# Application.net
KiCad netlist of a schematic drawn in EAGLE
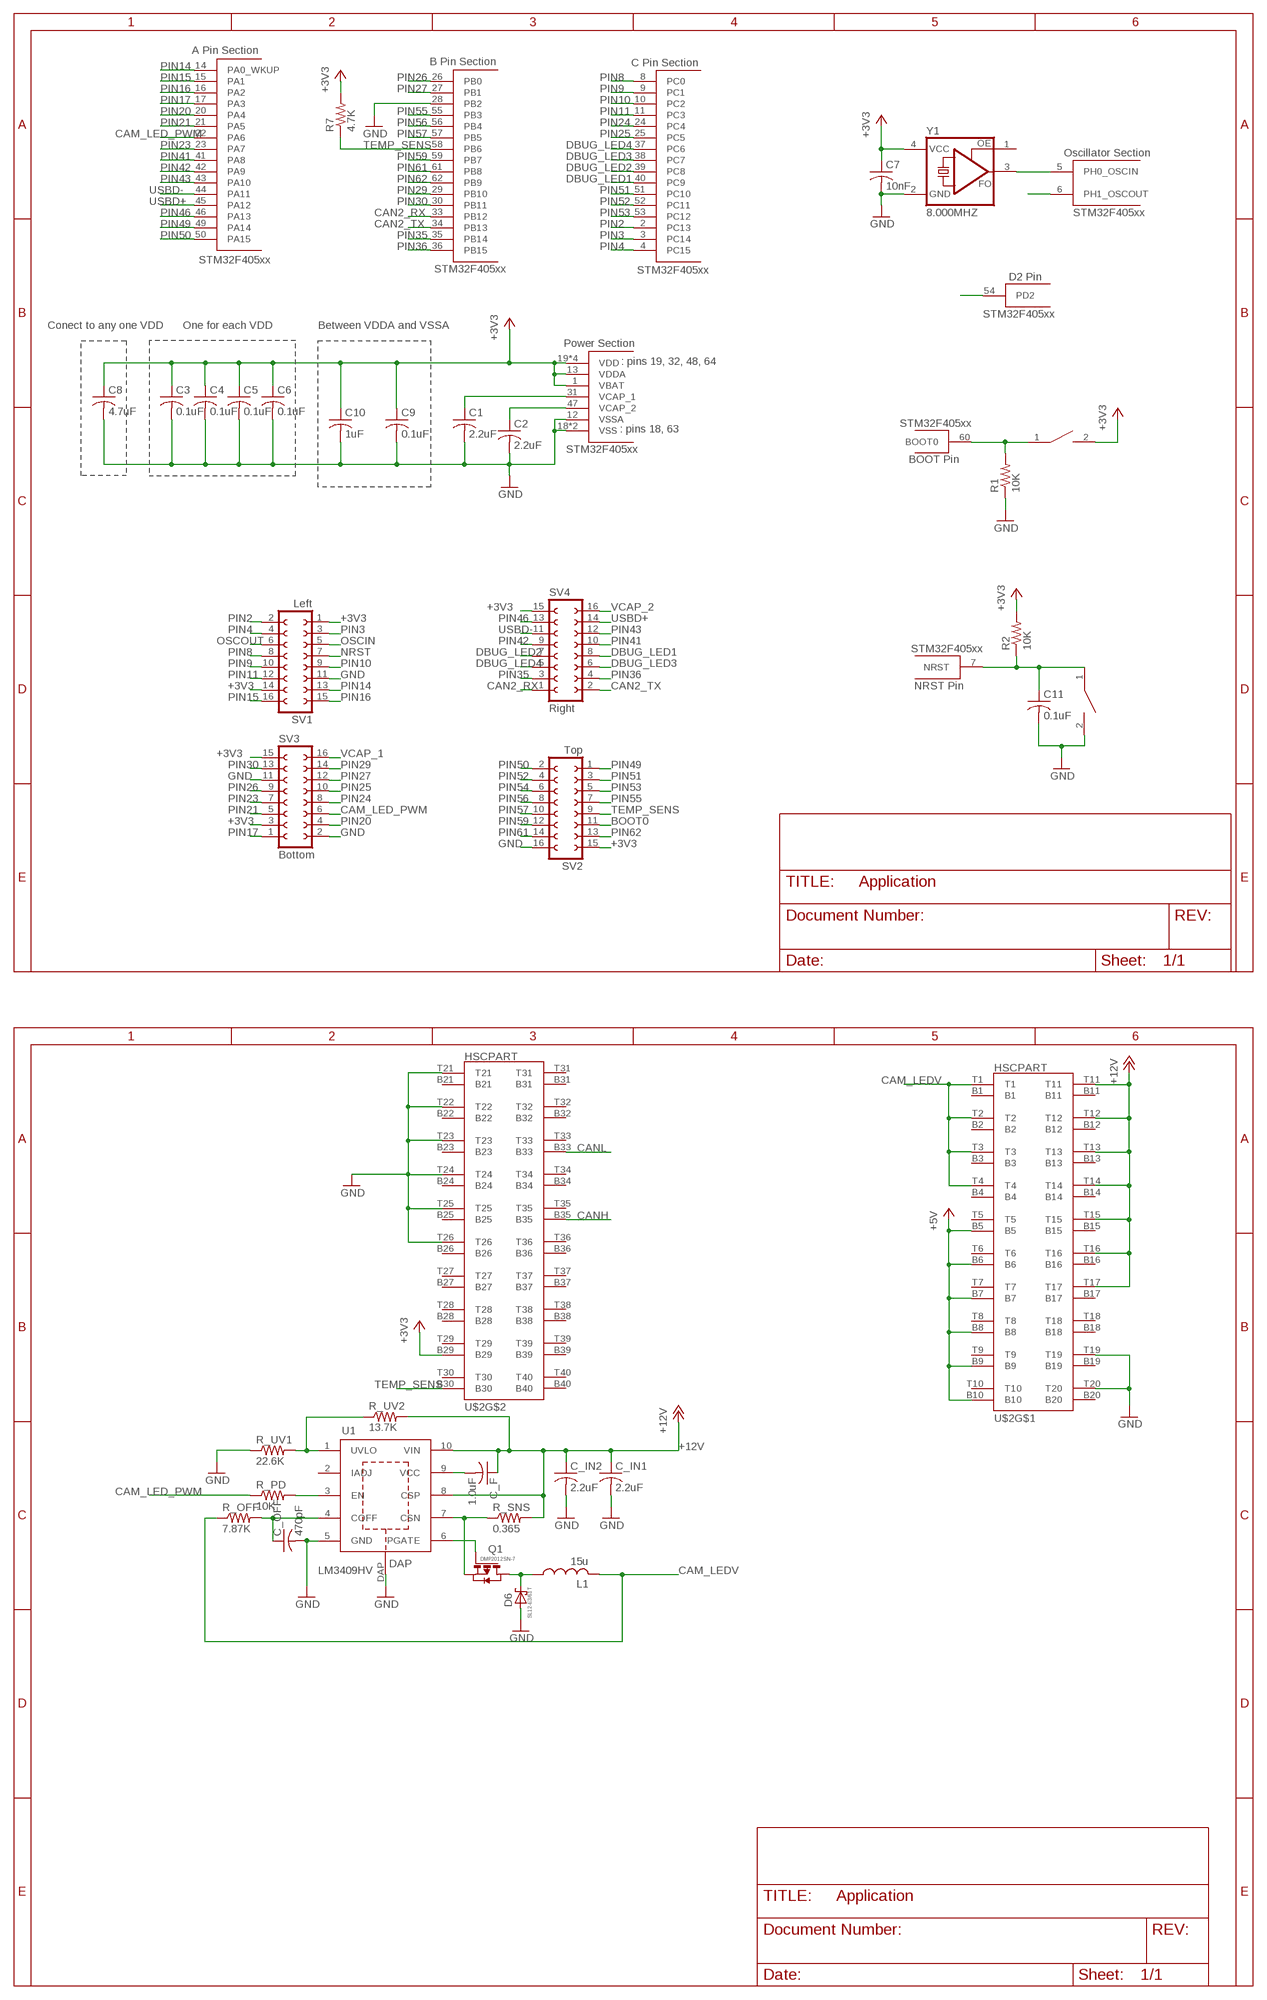
[diagram p0: schematic, sheet 1, part 1 of 2]
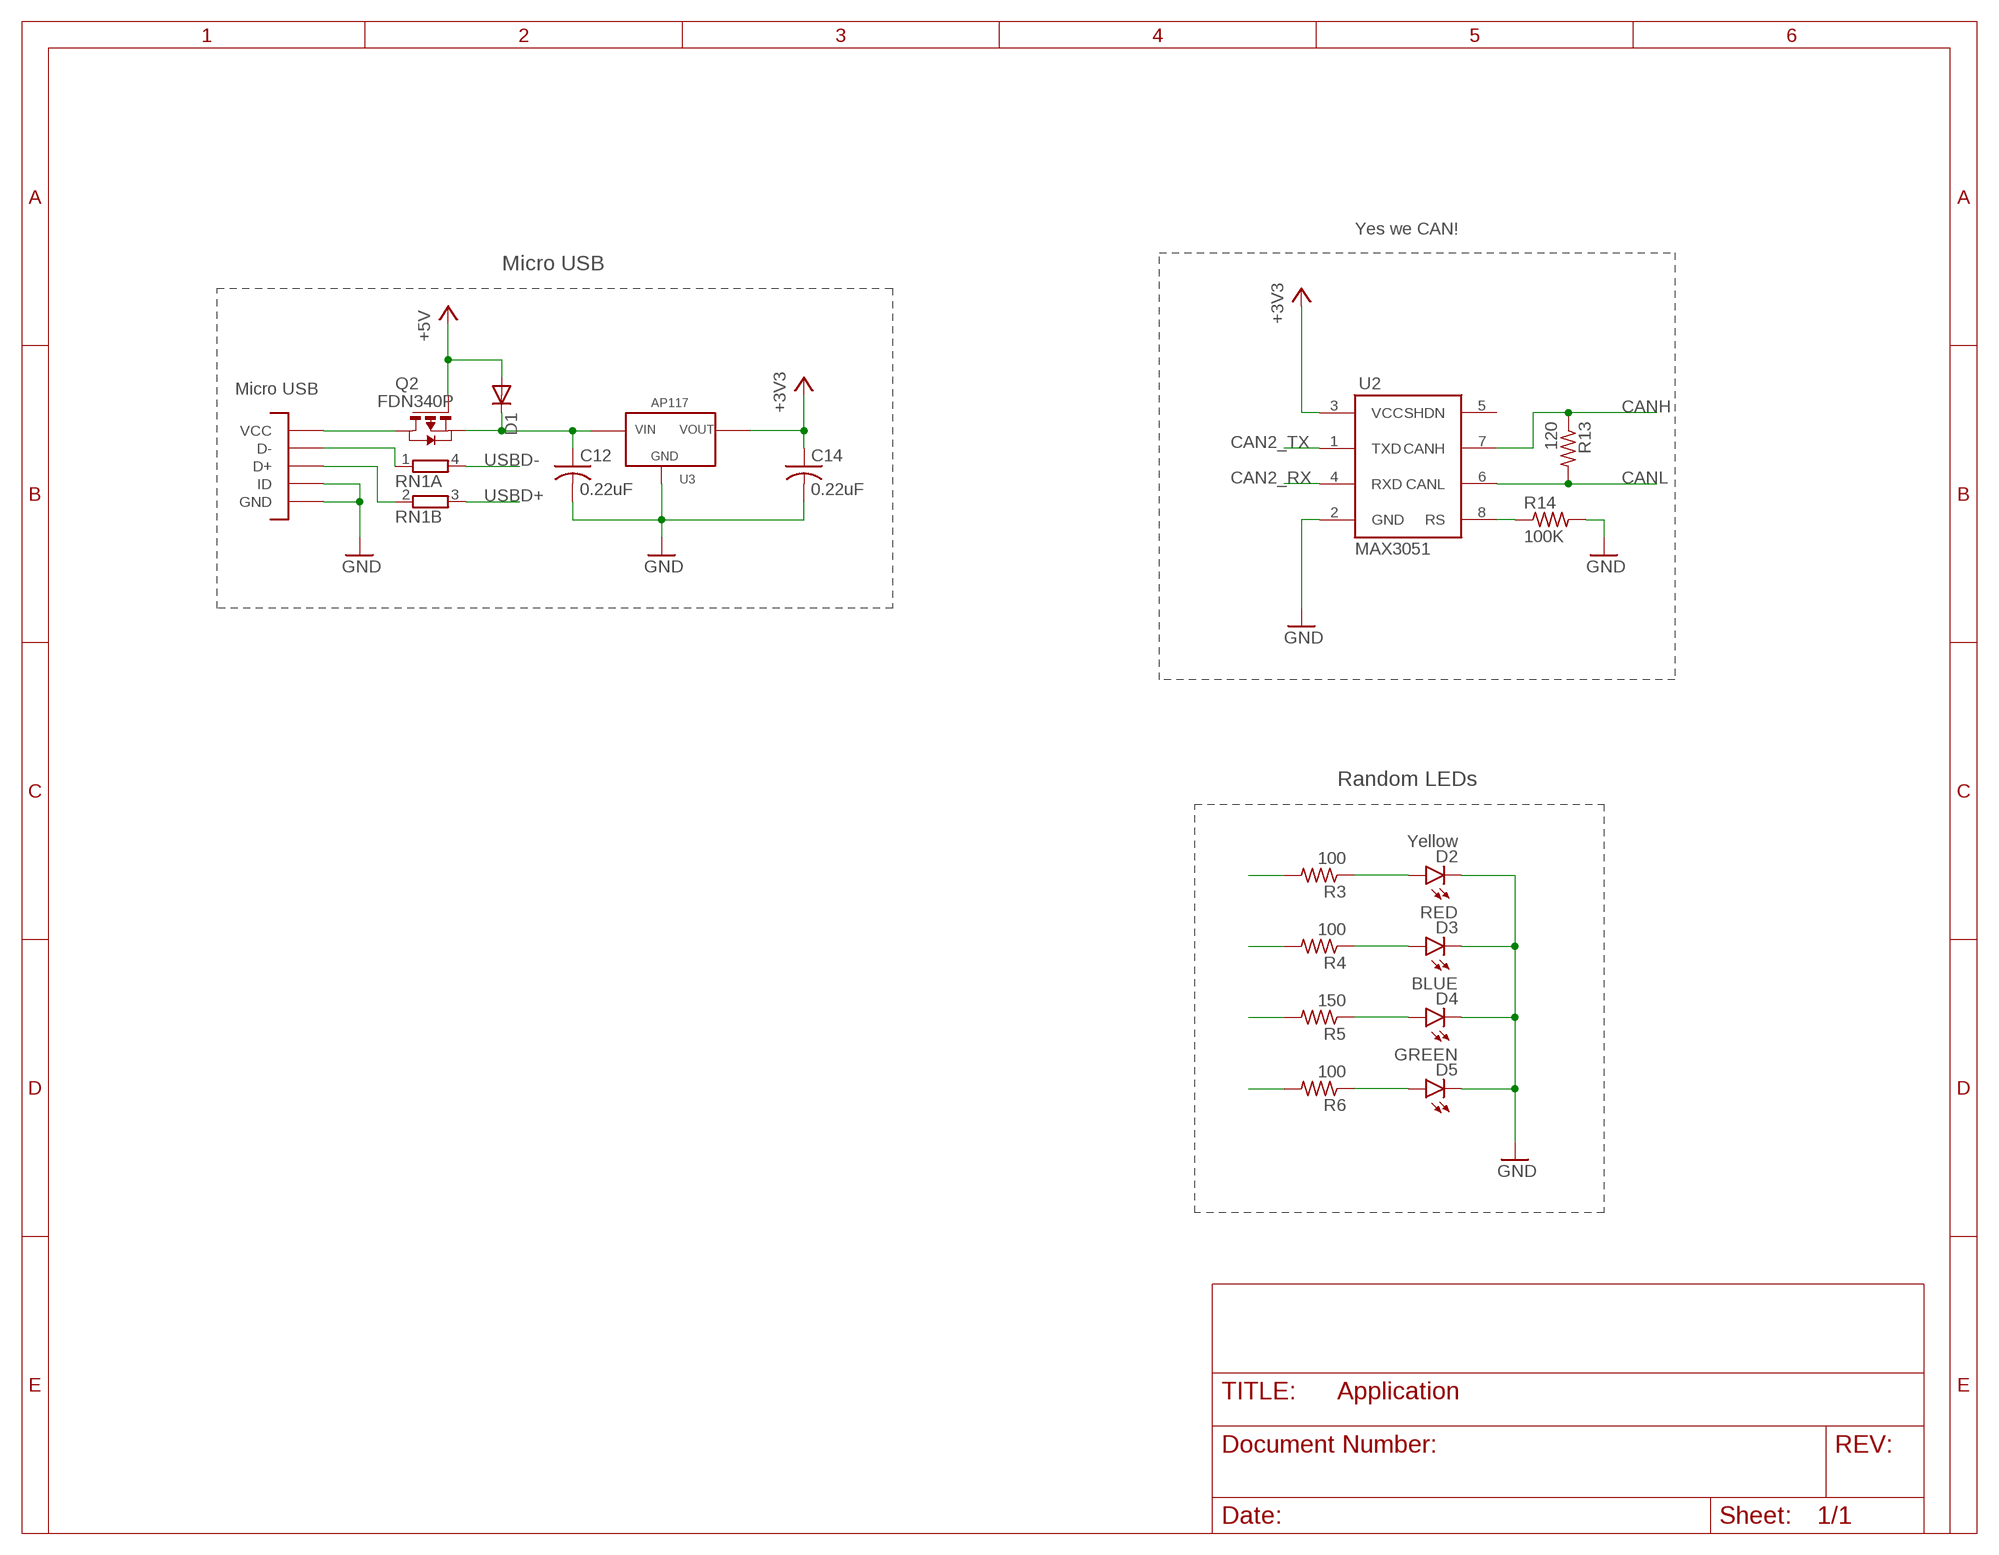
[diagram p1: schematic, sheet 1, part 2 of 2]

(export (version "E")
  (design (tool "Eeschema 10.0.6"))
  (components
    (comp (ref "C1")
      (value "2.2uF")
      (footprint "eagle-import:C0603")
      (libsource (lib "eagle-import") (part "C-USC0603"))
    )
    (comp (ref "C2")
      (value "2.2uF")
      (footprint "eagle-import:C0603")
      (libsource (lib "eagle-import") (part "C-USC0603"))
    )
    (comp (ref "C3")
      (value "0.1uF")
      (footprint "eagle-import:C0603")
      (libsource (lib "eagle-import") (part "C-USC0603"))
    )
    (comp (ref "C4")
      (value "0.1uF")
      (footprint "eagle-import:C0603")
      (libsource (lib "eagle-import") (part "C-USC0603"))
    )
    (comp (ref "C5")
      (value "0.1uF")
      (footprint "eagle-import:C0603")
      (libsource (lib "eagle-import") (part "C-USC0603"))
    )
    (comp (ref "C6")
      (value "0.1uF")
      (footprint "eagle-import:C0603")
      (libsource (lib "eagle-import") (part "C-USC0603"))
    )
    (comp (ref "C7")
      (value "10nF")
      (footprint "eagle-import:C0603")
      (libsource (lib "eagle-import") (part "C-USC0603"))
    )
    (comp (ref "C8")
      (value "4.7uF")
      (footprint "eagle-import:C0603")
      (libsource (lib "eagle-import") (part "C-USC0603"))
    )
    (comp (ref "C9")
      (value "0.1uF")
      (footprint "eagle-import:C0603")
      (libsource (lib "eagle-import") (part "C-USC0603"))
    )
    (comp (ref "C10")
      (value "1uF")
      (footprint "eagle-import:C0603")
      (libsource (lib "eagle-import") (part "C-USC0603"))
    )
    (comp (ref "C11")
      (value "0.1uF")
      (footprint "eagle-import:C0603")
      (libsource (lib "eagle-import") (part "C-USC0603"))
    )
    (comp (ref "C12")
      (value "0.22uF")
      (footprint "eagle-import:C0603")
      (libsource (lib "eagle-import") (part "C-USC0603"))
    )
    (comp (ref "C14")
      (value "0.22uF")
      (footprint "eagle-import:C0603")
      (libsource (lib "eagle-import") (part "C-USC0603"))
    )
    (comp (ref "C_F")
      (value "1.0uF")
      (footprint "eagle-import:C0603")
      (libsource (lib "eagle-import") (part "resistor_C-USC0603"))
    )
    (comp (ref "C_IN1")
      (value "2.2uF")
      (footprint "eagle-import:C0603")
      (libsource (lib "eagle-import") (part "resistor_C-USC0603"))
    )
    (comp (ref "C_IN2")
      (value "2.2uF")
      (footprint "eagle-import:C0603")
      (libsource (lib "eagle-import") (part "resistor_C-USC0603"))
    )
    (comp (ref "C_OFF")
      (value "470pF")
      (footprint "eagle-import:C0603")
      (libsource (lib "eagle-import") (part "resistor_C-USC0603"))
    )
    (comp (ref "D1")
      (value "DIODE-DO-214AC")
      (footprint "eagle-import:DO-214AC")
      (libsource (lib "eagle-import") (part "DIODE-DO-214AC"))
    )
    (comp (ref "D2")
      (value "Yellow")
      (footprint "eagle-import:LED-0603")
      (libsource (lib "eagle-import") (part "LED-YELLOW0603"))
    )
    (comp (ref "D3")
      (value "RED")
      (footprint "eagle-import:LED-0603")
      (libsource (lib "eagle-import") (part "LED-RED0603"))
    )
    (comp (ref "D4")
      (value "BLUE")
      (footprint "eagle-import:LED-0603")
      (libsource (lib "eagle-import") (part "LED-BLUE0603"))
    )
    (comp (ref "D5")
      (value "GREEN")
      (footprint "eagle-import:LED-0603")
      (libsource (lib "eagle-import") (part "LED-GREEN0603"))
    )
    (comp (ref "D6")
      (value "SL12-E3/61T")
      (footprint "eagle-import:SL12-E3_61T")
      (libsource (lib "eagle-import") (part "SL12-E3/61T"))
    )
    (comp (ref "L1")
      (value "15u")
      (footprint "eagle-import:SRN8040")
      (libsource (lib "eagle-import") (part "SRN8040"))
    )
    (comp (ref "Q1")
      (value "DMP2012SN-7")
      (footprint "eagle-import:DMP2012SN-7")
      (libsource (lib "eagle-import") (part "DMP2012SN-7"))
    )
    (comp (ref "Q2")
      (value "FDN340P")
      (footprint "eagle-import:SOT-23")
      (libsource (lib "eagle-import") (part "FDN340P"))
    )
    (comp (ref "R1")
      (value "10K")
      (footprint "eagle-import:R0603")
      (libsource (lib "eagle-import") (part "rcl_R-US_R0603"))
    )
    (comp (ref "R2")
      (value "10K")
      (footprint "eagle-import:R0603")
      (libsource (lib "eagle-import") (part "rcl_R-US_R0603"))
    )
    (comp (ref "R3")
      (value "100")
      (footprint "eagle-import:R0603")
      (libsource (lib "eagle-import") (part "rcl_R-US_R0603"))
    )
    (comp (ref "R4")
      (value "100")
      (footprint "eagle-import:R0603")
      (libsource (lib "eagle-import") (part "rcl_R-US_R0603"))
    )
    (comp (ref "R5")
      (value "150")
      (footprint "eagle-import:R0603")
      (libsource (lib "eagle-import") (part "rcl_R-US_R0603"))
    )
    (comp (ref "R6")
      (value "100")
      (footprint "eagle-import:R0603")
      (libsource (lib "eagle-import") (part "rcl_R-US_R0603"))
    )
    (comp (ref "R7")
      (value "4.7K")
      (footprint "eagle-import:R0603")
      (libsource (lib "eagle-import") (part "rcl_R-US_R0603"))
    )
    (comp (ref "R13")
      (value "120")
      (footprint "eagle-import:R0603")
      (libsource (lib "eagle-import") (part "rcl_R-US_R0603"))
    )
    (comp (ref "R14")
      (value "100K")
      (footprint "eagle-import:R0603")
      (libsource (lib "eagle-import") (part "rcl_R-US_R0603"))
    )
    (comp (ref "RN1")
      (value "2R-NEXBV4V")
      (footprint "eagle-import:EXBV4V")
      (fields (field (name "MF") "Rohm Semiconductor") (field (name "MPN") "MNR12ERAPJ220"))
      (libsource (lib "eagle-import") (part "2R-NEXBV4V"))
    )
    (comp (ref "R_OFF")
      (value "7.87K")
      (footprint "eagle-import:R0603")
      (libsource (lib "eagle-import") (part "R-US_R0603"))
    )
    (comp (ref "R_PD")
      (value "10K")
      (footprint "eagle-import:R0603")
      (libsource (lib "eagle-import") (part "R-US_R0603"))
    )
    (comp (ref "R_SNS")
      (value "0.365")
      (footprint "eagle-import:R2512")
      (libsource (lib "eagle-import") (part "R-US_R2512"))
    )
    (comp (ref "R_UV1")
      (value "22.6K")
      (footprint "eagle-import:R0603")
      (libsource (lib "eagle-import") (part "R-US_R0603"))
    )
    (comp (ref "R_UV2")
      (value "13.7K")
      (footprint "eagle-import:R0603")
      (libsource (lib "eagle-import") (part "R-US_R0603"))
    )
    (comp (ref "S1")
      (value "BOOT")
      (footprint "eagle-import:SW_2512")
      (libsource (lib "eagle-import") (part "SWITCH"))
    )
    (comp (ref "S2")
      (value "RESET")
      (footprint "eagle-import:SW_2512")
      (libsource (lib "eagle-import") (part "SWITCH"))
    )
    (comp (ref "SV1")
      (value "Left")
      (footprint "eagle-import:FE08-2")
      (libsource (lib "eagle-import") (part "FE08-2"))
    )
    (comp (ref "SV2")
      (value "Top")
      (footprint "eagle-import:FE08-2")
      (libsource (lib "eagle-import") (part "FE08-2"))
    )
    (comp (ref "SV3")
      (value "Bottom")
      (footprint "eagle-import:FE08-2")
      (libsource (lib "eagle-import") (part "FE08-2"))
    )
    (comp (ref "SV4")
      (value "Right")
      (footprint "eagle-import:FE08-2")
      (libsource (lib "eagle-import") (part "FE08-2"))
    )
    (comp (ref "U$2")
      (value "HSCPART")
      (footprint "eagle-import:HSC8-40PINOUUT")
      (libsource (lib "eagle-import") (part "HSCPART"))
    )
    (comp (ref "U1")
      (value "LM3409HV")
      (footprint "eagle-import:VSSOP-10")
      (libsource (lib "eagle-import") (part "LM3409HV'LM3409HV'"))
    )
    (comp (ref "U2")
      (value "MAX3051")
      (footprint "eagle-import:SOT23-8L")
      (libsource (lib "eagle-import") (part "MAX3051MAX3051"))
    )
    (comp (ref "U3")
      (value "U3")
      (footprint "eagle-import:SOT223")
      (libsource (lib "eagle-import") (part "AP1117_LIN_REG"))
    )
    (comp (ref "U4")
      (value "STM32F405")
      (footprint "eagle-import:LQFP64")
      (libsource (lib "eagle-import") (part "STM32F405"))
    )
    (comp (ref "U5")
      (value "MICROUSB")
      (footprint "eagle-import:MICRO_B")
      (libsource (lib "eagle-import") (part "MICROUSB"))
    )
    (comp (ref "Y1")
      (value "8.000MHZ")
      (footprint "eagle-import:ASF")
      (libsource (lib "eagle-import") (part "ASF"))
    )
  )
  (nets
    (net (code "1") (name "+3V3") (class "Default")
      (node (ref "C10") (pin "1") (pinfunction "1_1") (pintype "passive"))
      (node (ref "C14") (pin "1") (pinfunction "1_1") (pintype "passive"))
      (node (ref "C3") (pin "1") (pinfunction "1_1") (pintype "passive"))
      (node (ref "C4") (pin "1") (pinfunction "1_1") (pintype "passive"))
      (node (ref "C5") (pin "1") (pinfunction "1_1") (pintype "passive"))
      (node (ref "C6") (pin "1") (pinfunction "1_1") (pintype "passive"))
      (node (ref "C7") (pin "1") (pinfunction "1_1") (pintype "passive"))
      (node (ref "C8") (pin "1") (pinfunction "1_1") (pintype "passive"))
      (node (ref "C9") (pin "1") (pinfunction "1_1") (pintype "passive"))
      (node (ref "R2") (pin "2") (pinfunction "2_2") (pintype "passive"))
      (node (ref "R7") (pin "2") (pinfunction "2_2") (pintype "passive"))
      (node (ref "S1") (pin "2") (pinfunction "P$2_2") (pintype "bidirectional"))
      (node (ref "SV1") (pin "1") (pinfunction "1_1") (pintype "passive"))
      (node (ref "SV1") (pin "14") (pinfunction "14_14") (pintype "passive"))
      (node (ref "SV2") (pin "15") (pinfunction "15_15") (pintype "passive"))
      (node (ref "SV3") (pin "15") (pinfunction "15_15") (pintype "passive"))
      (node (ref "SV3") (pin "3") (pinfunction "3_3") (pintype "passive"))
      (node (ref "SV4") (pin "15") (pinfunction "15_15") (pintype "passive"))
      (node (ref "U$2") (pin "B29") (pinfunction "B29_B29") (pintype "bidirectional"))
      (node (ref "U2") (pin "3") (pinfunction "VCC_3") (pintype "bidirectional"))
      (node (ref "U3") (pin "TAB") (pinfunction "VOUT_TAB") (pintype "output"))
      (node (ref "U3") (pin "VOUT") (pinfunction "VOUT_VOUT") (pintype "output"))
      (node (ref "U4") (pin "1") (pinfunction "VBAT_1") (pintype "bidirectional"))
      (node (ref "U4") (pin "13") (pinfunction "VDDA_13") (pintype "bidirectional"))
      (node (ref "U4") (pin "19") (pinfunction "VDD_19") (pintype "bidirectional"))
      (node (ref "U4") (pin "32") (pinfunction "VDD_32") (pintype "bidirectional"))
      (node (ref "U4") (pin "48") (pinfunction "VDD_48") (pintype "bidirectional"))
      (node (ref "U4") (pin "64") (pinfunction "VDD_64") (pintype "bidirectional"))
      (node (ref "Y1") (pin "4") (pinfunction "VCC_4") (pintype "power_in"))
    )
    (net (code "2") (name "+5V") (class "Default")
      (node (ref "D1") (pin "A") (pinfunction "A_A") (pintype "passive"))
      (node (ref "Q2") (pin "3") (pinfunction "G_3") (pintype "passive"))
      (node (ref "U$2") (pin "B10") (pinfunction "B10_B10") (pintype "bidirectional"))
      (node (ref "U$2") (pin "B5") (pinfunction "B5_B5") (pintype "bidirectional"))
      (node (ref "U$2") (pin "B6") (pinfunction "B6_B6") (pintype "bidirectional"))
      (node (ref "U$2") (pin "B7") (pinfunction "B7_B7") (pintype "bidirectional"))
      (node (ref "U$2") (pin "B8") (pinfunction "B8_B8") (pintype "bidirectional"))
      (node (ref "U$2") (pin "B9") (pinfunction "B9_B9") (pintype "bidirectional"))
    )
    (net (code "3") (name "+12V") (class "Default")
      (node (ref "C_F") (pin "1") (pinfunction "1_1") (pintype "passive"))
      (node (ref "C_IN1") (pin "1") (pinfunction "1_1") (pintype "passive"))
      (node (ref "C_IN2") (pin "1") (pinfunction "1_1") (pintype "passive"))
      (node (ref "R_SNS") (pin "2") (pinfunction "2_2") (pintype "passive"))
      (node (ref "R_UV2") (pin "2") (pinfunction "2_2") (pintype "passive"))
      (node (ref "U$2") (pin "T11") (pinfunction "T11_T11") (pintype "bidirectional"))
      (node (ref "U$2") (pin "T12") (pinfunction "T12_T12") (pintype "bidirectional"))
      (node (ref "U$2") (pin "T13") (pinfunction "T13_T13") (pintype "bidirectional"))
      (node (ref "U$2") (pin "T14") (pinfunction "T14_T14") (pintype "bidirectional"))
      (node (ref "U$2") (pin "T15") (pinfunction "T15_T15") (pintype "bidirectional"))
      (node (ref "U$2") (pin "T16") (pinfunction "T16_T16") (pintype "bidirectional"))
      (node (ref "U$2") (pin "T17") (pinfunction "T17_T17") (pintype "bidirectional"))
      (node (ref "U1") (pin "10") (pinfunction "VIN_10") (pintype "bidirectional"))
      (node (ref "U1") (pin "8") (pinfunction "CSP_8") (pintype "bidirectional"))
    )
    (net (code "4") (name "/BOOT0") (class "Default")
      (node (ref "R1") (pin "2") (pinfunction "2_2") (pintype "passive"))
      (node (ref "S1") (pin "1") (pinfunction "P$1_1") (pintype "bidirectional"))
      (node (ref "SV2") (pin "11") (pinfunction "11_11") (pintype "passive"))
      (node (ref "U4") (pin "60") (pinfunction "BOOT0_60") (pintype "bidirectional"))
    )
    (net (code "5") (name "/CAM_LEDV") (class "Default")
      (node (ref "L1") (pin "2") (pinfunction "2_2") (pintype "passive"))
      (node (ref "R_OFF") (pin "1") (pinfunction "1_1") (pintype "passive"))
      (node (ref "U$2") (pin "T1") (pinfunction "T1_T1") (pintype "bidirectional"))
      (node (ref "U$2") (pin "T2") (pinfunction "T2_T2") (pintype "bidirectional"))
      (node (ref "U$2") (pin "T3") (pinfunction "T3_T3") (pintype "bidirectional"))
      (node (ref "U$2") (pin "T4") (pinfunction "T4_T4") (pintype "bidirectional"))
    )
    (net (code "6") (name "/CAM_LED_PWM") (class "Default")
      (node (ref "R_PD") (pin "1") (pinfunction "1_1") (pintype "passive"))
      (node (ref "SV3") (pin "6") (pinfunction "6_6") (pintype "passive"))
      (node (ref "U4") (pin "22") (pinfunction "PA6_22") (pintype "bidirectional"))
    )
    (net (code "7") (name "/CAN2_RX") (class "Default")
      (node (ref "SV4") (pin "1") (pinfunction "1_1") (pintype "passive"))
      (node (ref "U2") (pin "4") (pinfunction "RXD_4") (pintype "bidirectional"))
      (node (ref "U4") (pin "33") (pinfunction "PB12_33") (pintype "bidirectional"))
    )
    (net (code "8") (name "/CAN2_TX") (class "Default")
      (node (ref "SV4") (pin "2") (pinfunction "2_2") (pintype "passive"))
      (node (ref "U2") (pin "1") (pinfunction "TXD_1") (pintype "bidirectional"))
      (node (ref "U4") (pin "34") (pinfunction "PB13_34") (pintype "bidirectional"))
    )
    (net (code "9") (name "/CANH") (class "Default")
      (node (ref "R13") (pin "1") (pinfunction "1_1") (pintype "passive"))
      (node (ref "U$2") (pin "B35") (pinfunction "B35_B35") (pintype "bidirectional"))
      (node (ref "U2") (pin "7") (pinfunction "CANH_7") (pintype "bidirectional"))
    )
    (net (code "10") (name "/CANL") (class "Default")
      (node (ref "R13") (pin "2") (pinfunction "2_2") (pintype "passive"))
      (node (ref "U$2") (pin "B33") (pinfunction "B33_B33") (pintype "bidirectional"))
      (node (ref "U2") (pin "6") (pinfunction "CANL_6") (pintype "bidirectional"))
    )
    (net (code "11") (name "/DBUG_LED1") (class "Default")
      (node (ref "R3") (pin "2") (pinfunction "2_2") (pintype "passive"))
      (node (ref "SV4") (pin "8") (pinfunction "8_8") (pintype "passive"))
      (node (ref "U4") (pin "40") (pinfunction "PC9_40") (pintype "bidirectional"))
    )
    (net (code "12") (name "/DBUG_LED2") (class "Default")
      (node (ref "R4") (pin "2") (pinfunction "2_2") (pintype "passive"))
      (node (ref "SV4") (pin "7") (pinfunction "7_7") (pintype "passive"))
      (node (ref "U4") (pin "39") (pinfunction "PC8_39") (pintype "bidirectional"))
    )
    (net (code "13") (name "/DBUG_LED3") (class "Default")
      (node (ref "R5") (pin "2") (pinfunction "2_2") (pintype "passive"))
      (node (ref "SV4") (pin "6") (pinfunction "6_6") (pintype "passive"))
      (node (ref "U4") (pin "38") (pinfunction "PC7_38") (pintype "bidirectional"))
    )
    (net (code "14") (name "/DBUG_LED4") (class "Default")
      (node (ref "R6") (pin "2") (pinfunction "2_2") (pintype "passive"))
      (node (ref "SV4") (pin "5") (pinfunction "5_5") (pintype "passive"))
      (node (ref "U4") (pin "37") (pinfunction "PC6_37") (pintype "bidirectional"))
    )
    (net (code "15") (name "/NRST") (class "Default")
      (node (ref "C11") (pin "1") (pinfunction "1_1") (pintype "passive"))
      (node (ref "R2") (pin "1") (pinfunction "1_1") (pintype "passive"))
      (node (ref "S2") (pin "1") (pinfunction "P$1_1") (pintype "bidirectional"))
      (node (ref "SV1") (pin "7") (pinfunction "7_7") (pintype "passive"))
      (node (ref "U4") (pin "7") (pinfunction "NRST_7") (pintype "bidirectional"))
    )
    (net (code "16") (name "/OSCIN") (class "Default")
      (node (ref "SV1") (pin "5") (pinfunction "5_5") (pintype "passive"))
      (node (ref "U4") (pin "5") (pinfunction "PH0_OSCIN_5") (pintype "bidirectional"))
      (node (ref "Y1") (pin "3") (pinfunction "FO_3") (pintype "output"))
    )
    (net (code "17") (name "/OSCOUT") (class "Default")
      (node (ref "SV1") (pin "6") (pinfunction "6_6") (pintype "passive"))
      (node (ref "U4") (pin "6") (pinfunction "PH1_OSCOUT_6") (pintype "bidirectional"))
    )
    (net (code "18") (name "/PIN2") (class "Default")
      (node (ref "SV1") (pin "2") (pinfunction "2_2") (pintype "passive"))
      (node (ref "U4") (pin "2") (pinfunction "PC13_2") (pintype "bidirectional"))
    )
    (net (code "19") (name "/PIN3") (class "Default")
      (node (ref "SV1") (pin "3") (pinfunction "3_3") (pintype "passive"))
      (node (ref "U4") (pin "3") (pinfunction "PC14_3") (pintype "bidirectional"))
    )
    (net (code "20") (name "/PIN4") (class "Default")
      (node (ref "SV1") (pin "4") (pinfunction "4_4") (pintype "passive"))
      (node (ref "U4") (pin "4") (pinfunction "PC15_4") (pintype "bidirectional"))
    )
    (net (code "21") (name "/PIN8") (class "Default")
      (node (ref "SV1") (pin "8") (pinfunction "8_8") (pintype "passive"))
      (node (ref "U4") (pin "8") (pinfunction "PC0_8") (pintype "bidirectional"))
    )
    (net (code "22") (name "/PIN9") (class "Default")
      (node (ref "SV1") (pin "10") (pinfunction "10_10") (pintype "passive"))
      (node (ref "U4") (pin "9") (pinfunction "PC1_9") (pintype "bidirectional"))
    )
    (net (code "23") (name "/PIN10") (class "Default")
      (node (ref "SV1") (pin "9") (pinfunction "9_9") (pintype "passive"))
      (node (ref "U4") (pin "10") (pinfunction "PC2_10") (pintype "bidirectional"))
    )
    (net (code "24") (name "/PIN11") (class "Default")
      (node (ref "SV1") (pin "12") (pinfunction "12_12") (pintype "passive"))
      (node (ref "U4") (pin "11") (pinfunction "PC3_11") (pintype "bidirectional"))
    )
    (net (code "25") (name "/PIN14") (class "Default")
      (node (ref "SV1") (pin "13") (pinfunction "13_13") (pintype "passive"))
      (node (ref "U4") (pin "14") (pinfunction "PA0_WKUP_14") (pintype "bidirectional"))
    )
    (net (code "26") (name "/PIN15") (class "Default")
      (node (ref "SV1") (pin "16") (pinfunction "16_16") (pintype "passive"))
      (node (ref "U4") (pin "15") (pinfunction "PA1_15") (pintype "bidirectional"))
    )
    (net (code "27") (name "/PIN16") (class "Default")
      (node (ref "SV1") (pin "15") (pinfunction "15_15") (pintype "passive"))
      (node (ref "U4") (pin "16") (pinfunction "PA2_16") (pintype "bidirectional"))
    )
    (net (code "28") (name "/PIN17") (class "Default")
      (node (ref "SV3") (pin "1") (pinfunction "1_1") (pintype "passive"))
      (node (ref "U4") (pin "17") (pinfunction "PA3_17") (pintype "bidirectional"))
    )
    (net (code "29") (name "/PIN20") (class "Default")
      (node (ref "SV3") (pin "4") (pinfunction "4_4") (pintype "passive"))
      (node (ref "U4") (pin "20") (pinfunction "PA4_20") (pintype "bidirectional"))
    )
    (net (code "30") (name "/PIN21") (class "Default")
      (node (ref "SV3") (pin "5") (pinfunction "5_5") (pintype "passive"))
      (node (ref "U4") (pin "21") (pinfunction "PA5_21") (pintype "bidirectional"))
    )
    (net (code "31") (name "/PIN23") (class "Default")
      (node (ref "SV3") (pin "7") (pinfunction "7_7") (pintype "passive"))
      (node (ref "U4") (pin "23") (pinfunction "PA7_23") (pintype "bidirectional"))
    )
    (net (code "32") (name "/PIN24") (class "Default")
      (node (ref "SV3") (pin "8") (pinfunction "8_8") (pintype "passive"))
      (node (ref "U4") (pin "24") (pinfunction "PC4_24") (pintype "bidirectional"))
    )
    (net (code "33") (name "/PIN25") (class "Default")
      (node (ref "SV3") (pin "10") (pinfunction "10_10") (pintype "passive"))
      (node (ref "U4") (pin "25") (pinfunction "PC5_25") (pintype "bidirectional"))
    )
    (net (code "34") (name "/PIN26") (class "Default")
      (node (ref "SV3") (pin "9") (pinfunction "9_9") (pintype "passive"))
      (node (ref "U4") (pin "26") (pinfunction "PB0_26") (pintype "bidirectional"))
    )
    (net (code "35") (name "/PIN27") (class "Default")
      (node (ref "SV3") (pin "12") (pinfunction "12_12") (pintype "passive"))
      (node (ref "U4") (pin "27") (pinfunction "PB1_27") (pintype "bidirectional"))
    )
    (net (code "36") (name "/PIN29") (class "Default")
      (node (ref "SV3") (pin "14") (pinfunction "14_14") (pintype "passive"))
      (node (ref "U4") (pin "29") (pinfunction "PB10_29") (pintype "bidirectional"))
    )
    (net (code "37") (name "/PIN30") (class "Default")
      (node (ref "SV3") (pin "13") (pinfunction "13_13") (pintype "passive"))
      (node (ref "U4") (pin "30") (pinfunction "PB11_30") (pintype "bidirectional"))
    )
    (net (code "38") (name "/PIN35") (class "Default")
      (node (ref "SV4") (pin "3") (pinfunction "3_3") (pintype "passive"))
      (node (ref "U4") (pin "35") (pinfunction "PB14_35") (pintype "bidirectional"))
    )
    (net (code "39") (name "/PIN36") (class "Default")
      (node (ref "SV4") (pin "4") (pinfunction "4_4") (pintype "passive"))
      (node (ref "U4") (pin "36") (pinfunction "PB15_36") (pintype "bidirectional"))
    )
    (net (code "40") (name "/PIN41") (class "Default")
      (node (ref "SV4") (pin "10") (pinfunction "10_10") (pintype "passive"))
      (node (ref "U4") (pin "41") (pinfunction "PA8_41") (pintype "bidirectional"))
    )
    (net (code "41") (name "/PIN42") (class "Default")
      (node (ref "SV4") (pin "9") (pinfunction "9_9") (pintype "passive"))
      (node (ref "U4") (pin "42") (pinfunction "PA9_42") (pintype "bidirectional"))
    )
    (net (code "42") (name "/PIN43") (class "Default")
      (node (ref "SV4") (pin "12") (pinfunction "12_12") (pintype "passive"))
      (node (ref "U4") (pin "43") (pinfunction "PA10_43") (pintype "bidirectional"))
    )
    (net (code "43") (name "/PIN46") (class "Default")
      (node (ref "SV4") (pin "13") (pinfunction "13_13") (pintype "passive"))
      (node (ref "U4") (pin "46") (pinfunction "PA13_46") (pintype "bidirectional"))
    )
    (net (code "44") (name "/PIN49") (class "Default")
      (node (ref "SV2") (pin "1") (pinfunction "1_1") (pintype "passive"))
      (node (ref "U4") (pin "49") (pinfunction "PA14_49") (pintype "bidirectional"))
    )
    (net (code "45") (name "/PIN50") (class "Default")
      (node (ref "SV2") (pin "2") (pinfunction "2_2") (pintype "passive"))
      (node (ref "U4") (pin "50") (pinfunction "PA15_50") (pintype "bidirectional"))
    )
    (net (code "46") (name "/PIN51") (class "Default")
      (node (ref "SV2") (pin "3") (pinfunction "3_3") (pintype "passive"))
      (node (ref "U4") (pin "51") (pinfunction "PC10_51") (pintype "bidirectional"))
    )
    (net (code "47") (name "/PIN52") (class "Default")
      (node (ref "SV2") (pin "4") (pinfunction "4_4") (pintype "passive"))
      (node (ref "U4") (pin "52") (pinfunction "PC11_52") (pintype "bidirectional"))
    )
    (net (code "48") (name "/PIN53") (class "Default")
      (node (ref "SV2") (pin "5") (pinfunction "5_5") (pintype "passive"))
      (node (ref "U4") (pin "53") (pinfunction "PC12_53") (pintype "bidirectional"))
    )
    (net (code "49") (name "/PIN54") (class "Default")
      (node (ref "SV2") (pin "6") (pinfunction "6_6") (pintype "passive"))
      (node (ref "U4") (pin "54") (pinfunction "PD2_54") (pintype "bidirectional"))
    )
    (net (code "50") (name "/PIN55") (class "Default")
      (node (ref "SV2") (pin "7") (pinfunction "7_7") (pintype "passive"))
      (node (ref "U4") (pin "55") (pinfunction "PB3_55") (pintype "bidirectional"))
    )
    (net (code "51") (name "/PIN56") (class "Default")
      (node (ref "SV2") (pin "8") (pinfunction "8_8") (pintype "passive"))
      (node (ref "U4") (pin "56") (pinfunction "PB4_56") (pintype "bidirectional"))
    )
    (net (code "52") (name "/PIN57") (class "Default")
      (node (ref "SV2") (pin "10") (pinfunction "10_10") (pintype "passive"))
      (node (ref "U4") (pin "57") (pinfunction "PB5_57") (pintype "bidirectional"))
    )
    (net (code "53") (name "/PIN59") (class "Default")
      (node (ref "SV2") (pin "12") (pinfunction "12_12") (pintype "passive"))
      (node (ref "U4") (pin "59") (pinfunction "PB7_59") (pintype "bidirectional"))
    )
    (net (code "54") (name "/PIN61") (class "Default")
      (node (ref "SV2") (pin "14") (pinfunction "14_14") (pintype "passive"))
      (node (ref "U4") (pin "61") (pinfunction "PB8_61") (pintype "bidirectional"))
    )
    (net (code "55") (name "/PIN62") (class "Default")
      (node (ref "SV2") (pin "13") (pinfunction "13_13") (pintype "passive"))
      (node (ref "U4") (pin "62") (pinfunction "PB9_62") (pintype "bidirectional"))
    )
    (net (code "56") (name "/TEMP_SENS") (class "Default")
      (node (ref "R7") (pin "1") (pinfunction "1_1") (pintype "passive"))
      (node (ref "SV2") (pin "9") (pinfunction "9_9") (pintype "passive"))
      (node (ref "U$2") (pin "B30") (pinfunction "B30_B30") (pintype "bidirectional"))
      (node (ref "U4") (pin "58") (pinfunction "PB6_58") (pintype "bidirectional"))
    )
    (net (code "57") (name "/USBD+") (class "Default")
      (node (ref "RN1") (pin "3") (pinfunction "2_3") (pintype "passive"))
      (node (ref "SV4") (pin "14") (pinfunction "14_14") (pintype "passive"))
      (node (ref "U4") (pin "45") (pinfunction "PA12_45") (pintype "bidirectional"))
    )
    (net (code "58") (name "/USBD-") (class "Default")
      (node (ref "RN1") (pin "4") (pinfunction "2_4") (pintype "passive"))
      (node (ref "SV4") (pin "11") (pinfunction "11_11") (pintype "passive"))
      (node (ref "U4") (pin "44") (pinfunction "PA11_44") (pintype "bidirectional"))
    )
    (net (code "59") (name "/VCAP_1") (class "Default")
      (node (ref "C1") (pin "1") (pinfunction "1_1") (pintype "passive"))
      (node (ref "SV3") (pin "16") (pinfunction "16_16") (pintype "passive"))
      (node (ref "U4") (pin "31") (pinfunction "VCAP_1_31") (pintype "bidirectional"))
    )
    (net (code "60") (name "/VCAP_2") (class "Default")
      (node (ref "C2") (pin "1") (pinfunction "1_1") (pintype "passive"))
      (node (ref "SV4") (pin "16") (pinfunction "16_16") (pintype "passive"))
      (node (ref "U4") (pin "47") (pinfunction "VCAP_2_47") (pintype "bidirectional"))
    )
    (net (code "61") (name "GND") (class "Default")
      (node (ref "C1") (pin "2") (pinfunction "2_2") (pintype "passive"))
      (node (ref "C10") (pin "2") (pinfunction "2_2") (pintype "passive"))
      (node (ref "C11") (pin "2") (pinfunction "2_2") (pintype "passive"))
      (node (ref "C12") (pin "2") (pinfunction "2_2") (pintype "passive"))
      (node (ref "C14") (pin "2") (pinfunction "2_2") (pintype "passive"))
      (node (ref "C2") (pin "2") (pinfunction "2_2") (pintype "passive"))
      (node (ref "C3") (pin "2") (pinfunction "2_2") (pintype "passive"))
      (node (ref "C4") (pin "2") (pinfunction "2_2") (pintype "passive"))
      (node (ref "C5") (pin "2") (pinfunction "2_2") (pintype "passive"))
      (node (ref "C6") (pin "2") (pinfunction "2_2") (pintype "passive"))
      (node (ref "C7") (pin "2") (pinfunction "2_2") (pintype "passive"))
      (node (ref "C8") (pin "2") (pinfunction "2_2") (pintype "passive"))
      (node (ref "C9") (pin "2") (pinfunction "2_2") (pintype "passive"))
      (node (ref "C_IN1") (pin "2") (pinfunction "2_2") (pintype "passive"))
      (node (ref "C_IN2") (pin "2") (pinfunction "2_2") (pintype "passive"))
      (node (ref "C_OFF") (pin "2") (pinfunction "2_2") (pintype "passive"))
      (node (ref "D2") (pin "C") (pinfunction "C_C") (pintype "passive"))
      (node (ref "D3") (pin "C") (pinfunction "C_C") (pintype "passive"))
      (node (ref "D4") (pin "C") (pinfunction "C_C") (pintype "passive"))
      (node (ref "D5") (pin "C") (pinfunction "C_C") (pintype "passive"))
      (node (ref "D6") (pin "2") (pinfunction "A_2") (pintype "passive"))
      (node (ref "R1") (pin "1") (pinfunction "1_1") (pintype "passive"))
      (node (ref "R14") (pin "2") (pinfunction "2_2") (pintype "passive"))
      (node (ref "R_UV1") (pin "1") (pinfunction "1_1") (pintype "passive"))
      (node (ref "S2") (pin "2") (pinfunction "P$2_2") (pintype "bidirectional"))
      (node (ref "SV1") (pin "11") (pinfunction "11_11") (pintype "passive"))
      (node (ref "SV2") (pin "16") (pinfunction "16_16") (pintype "passive"))
      (node (ref "SV3") (pin "11") (pinfunction "11_11") (pintype "passive"))
      (node (ref "SV3") (pin "2") (pinfunction "2_2") (pintype "passive"))
      (node (ref "U$2") (pin "T19") (pinfunction "T19_T19") (pintype "bidirectional"))
      (node (ref "U$2") (pin "T20") (pinfunction "T20_T20") (pintype "bidirectional"))
      (node (ref "U$2") (pin "T21") (pinfunction "T21_T21") (pintype "bidirectional"))
      (node (ref "U$2") (pin "T22") (pinfunction "T22_T22") (pintype "bidirectional"))
      (node (ref "U$2") (pin "T23") (pinfunction "T23_T23") (pintype "bidirectional"))
      (node (ref "U$2") (pin "T24") (pinfunction "T24_T24") (pintype "bidirectional"))
      (node (ref "U$2") (pin "T25") (pinfunction "T25_T25") (pintype "bidirectional"))
      (node (ref "U$2") (pin "T26") (pinfunction "T26_T26") (pintype "bidirectional"))
      (node (ref "U1") (pin "5") (pinfunction "GND_5") (pintype "bidirectional"))
      (node (ref "U1") (pin "DAP") (pinfunction "DAP_DAP") (pintype "bidirectional"))
      (node (ref "U2") (pin "2") (pinfunction "GND_2") (pintype "bidirectional"))
      (node (ref "U3") (pin "GND") (pinfunction "GND_GND") (pintype "bidirectional"))
      (node (ref "U4") (pin "12") (pinfunction "VSSA_12") (pintype "bidirectional"))
      (node (ref "U4") (pin "18") (pinfunction "VSS_18") (pintype "bidirectional"))
      (node (ref "U4") (pin "28") (pinfunction "PB2_28") (pintype "bidirectional"))
      (node (ref "U4") (pin "63") (pinfunction "VSS_63") (pintype "bidirectional"))
      (node (ref "U5") (pin "GND1") (pinfunction "GND_GND1") (pintype "bidirectional"))
      (node (ref "U5") (pin "GND2") (pinfunction "GND_GND2") (pintype "bidirectional"))
      (node (ref "U5") (pin "GND3") (pinfunction "GND_GND3") (pintype "bidirectional"))
      (node (ref "U5") (pin "GND4") (pinfunction "GND_GND4") (pintype "bidirectional"))
      (node (ref "U5") (pin "GND7") (pinfunction "GND_GND7") (pintype "bidirectional"))
      (node (ref "U5") (pin "GND8") (pinfunction "GND_GND8") (pintype "bidirectional"))
      (node (ref "U5") (pin "P4") (pinfunction "ID_P4") (pintype "bidirectional"))
      (node (ref "U5") (pin "P5") (pinfunction "GND_P5") (pintype "bidirectional"))
      (node (ref "Y1") (pin "2") (pinfunction "GND_2") (pintype "power_in"))
    )
    (net (code "62") (name "Net-(D2-PadA)") (class "Default")
      (node (ref "D2") (pin "A") (pinfunction "A_A") (pintype "passive"))
      (node (ref "R3") (pin "1") (pinfunction "1_1") (pintype "passive"))
    )
    (net (code "63") (name "Net-(D3-PadA)") (class "Default")
      (node (ref "D3") (pin "A") (pinfunction "A_A") (pintype "passive"))
      (node (ref "R4") (pin "1") (pinfunction "1_1") (pintype "passive"))
    )
    (net (code "64") (name "Net-(D4-PadA)") (class "Default")
      (node (ref "D4") (pin "A") (pinfunction "A_A") (pintype "passive"))
      (node (ref "R5") (pin "1") (pinfunction "1_1") (pintype "passive"))
    )
    (net (code "65") (name "Net-(D5-PadA)") (class "Default")
      (node (ref "D5") (pin "A") (pinfunction "A_A") (pintype "passive"))
      (node (ref "R6") (pin "1") (pinfunction "1_1") (pintype "passive"))
    )
    (net (code "66") (name "Net-(D6-C)") (class "Default")
      (node (ref "D6") (pin "1") (pinfunction "C_1") (pintype "passive"))
      (node (ref "L1") (pin "1") (pinfunction "1_1") (pintype "passive"))
      (node (ref "Q1") (pin "1") (pinfunction "D_1") (pintype "passive"))
    )
    (net (code "67") (name "Net-(Q1-G)") (class "Default")
      (node (ref "Q1") (pin "2") (pinfunction "G_2") (pintype "passive"))
      (node (ref "U1") (pin "6") (pinfunction "PGATE_6") (pintype "bidirectional"))
    )
    (net (code "68") (name "Net-(Q1-S)") (class "Default")
      (node (ref "Q1") (pin "3") (pinfunction "S_3") (pintype "passive"))
      (node (ref "R_SNS") (pin "1") (pinfunction "1_1") (pintype "passive"))
      (node (ref "U1") (pin "7") (pinfunction "CSN_7") (pintype "bidirectional"))
    )
    (net (code "69") (name "Net-(Q2-D)") (class "Default")
      (node (ref "Q2") (pin "1") (pinfunction "D_1") (pintype "passive"))
      (node (ref "U5") (pin "P1") (pinfunction "VCC_P1") (pintype "bidirectional"))
    )
    (net (code "70") (name "Net-(Q2-S)") (class "Default")
      (node (ref "C12") (pin "1") (pinfunction "1_1") (pintype "passive"))
      (node (ref "D1") (pin "C") (pinfunction "C_C") (pintype "passive"))
      (node (ref "Q2") (pin "2") (pinfunction "S_2") (pintype "passive"))
      (node (ref "U3") (pin "VIN") (pinfunction "VIN_VIN") (pintype "input"))
    )
    (net (code "71") (name "Net-(RN1B-1)") (class "Default")
      (node (ref "RN1") (pin "2") (pinfunction "1_2") (pintype "passive"))
      (node (ref "U5") (pin "P3") (pinfunction "D+_P3") (pintype "bidirectional"))
    )
    (net (code "72") (name "Net-(U1-COFF)") (class "Default")
      (node (ref "C_OFF") (pin "1") (pinfunction "1_1") (pintype "passive"))
      (node (ref "R_OFF") (pin "2") (pinfunction "2_2") (pintype "passive"))
      (node (ref "U1") (pin "4") (pinfunction "COFF_4") (pintype "bidirectional"))
    )
    (net (code "73") (name "Net-(U1-EN)") (class "Default")
      (node (ref "R_PD") (pin "2") (pinfunction "2_2") (pintype "passive"))
      (node (ref "U1") (pin "3") (pinfunction "EN_3") (pintype "bidirectional"))
    )
    (net (code "74") (name "Net-(U1-UVLO)") (class "Default")
      (node (ref "R_UV1") (pin "2") (pinfunction "2_2") (pintype "passive"))
      (node (ref "R_UV2") (pin "1") (pinfunction "1_1") (pintype "passive"))
      (node (ref "U1") (pin "1") (pinfunction "UVLO_1") (pintype "bidirectional"))
    )
    (net (code "75") (name "Net-(U1-VCC)") (class "Default")
      (node (ref "C_F") (pin "2") (pinfunction "2_2") (pintype "passive"))
      (node (ref "U1") (pin "9") (pinfunction "VCC_9") (pintype "bidirectional"))
    )
    (net (code "76") (name "Net-(U2-RS)") (class "Default")
      (node (ref "R14") (pin "1") (pinfunction "1_1") (pintype "passive"))
      (node (ref "U2") (pin "8") (pinfunction "RS_8") (pintype "bidirectional"))
    )
    (net (code "77") (name "Net-(U5-D-)") (class "Default")
      (node (ref "RN1") (pin "1") (pinfunction "1_1") (pintype "passive"))
      (node (ref "U5") (pin "P2") (pinfunction "D-_P2") (pintype "bidirectional"))
    )
    (net (code "78") (name "unconnected-(U$2-PadB1)") (class "Default")
      (node (ref "U$2") (pin "B1") (pinfunction "B1_B1") (pintype "bidirectional"))
    )
    (net (code "79") (name "unconnected-(U$2-PadB2)") (class "Default")
      (node (ref "U$2") (pin "B2") (pinfunction "B2_B2") (pintype "bidirectional"))
    )
    (net (code "80") (name "unconnected-(U$2-PadB3)") (class "Default")
      (node (ref "U$2") (pin "B3") (pinfunction "B3_B3") (pintype "bidirectional"))
    )
    (net (code "81") (name "unconnected-(U$2-PadB4)") (class "Default")
      (node (ref "U$2") (pin "B4") (pinfunction "B4_B4") (pintype "bidirectional"))
    )
    (net (code "82") (name "unconnected-(U$2-PadB11)") (class "Default")
      (node (ref "U$2") (pin "B11") (pinfunction "B11_B11") (pintype "bidirectional"))
    )
    (net (code "83") (name "unconnected-(U$2-PadB12)") (class "Default")
      (node (ref "U$2") (pin "B12") (pinfunction "B12_B12") (pintype "bidirectional"))
    )
    (net (code "84") (name "unconnected-(U$2-PadB13)") (class "Default")
      (node (ref "U$2") (pin "B13") (pinfunction "B13_B13") (pintype "bidirectional"))
    )
    (net (code "85") (name "unconnected-(U$2-PadB14)") (class "Default")
      (node (ref "U$2") (pin "B14") (pinfunction "B14_B14") (pintype "bidirectional"))
    )
    (net (code "86") (name "unconnected-(U$2-PadB15)") (class "Default")
      (node (ref "U$2") (pin "B15") (pinfunction "B15_B15") (pintype "bidirectional"))
    )
    (net (code "87") (name "unconnected-(U$2-PadB16)") (class "Default")
      (node (ref "U$2") (pin "B16") (pinfunction "B16_B16") (pintype "bidirectional"))
    )
    (net (code "88") (name "unconnected-(U$2-PadB17)") (class "Default")
      (node (ref "U$2") (pin "B17") (pinfunction "B17_B17") (pintype "bidirectional"))
    )
    (net (code "89") (name "unconnected-(U$2-PadB18)") (class "Default")
      (node (ref "U$2") (pin "B18") (pinfunction "B18_B18") (pintype "bidirectional"))
    )
    (net (code "90") (name "unconnected-(U$2-PadB19)") (class "Default")
      (node (ref "U$2") (pin "B19") (pinfunction "B19_B19") (pintype "bidirectional"))
    )
    (net (code "91") (name "unconnected-(U$2-PadB20)") (class "Default")
      (node (ref "U$2") (pin "B20") (pinfunction "B20_B20") (pintype "bidirectional"))
    )
    (net (code "92") (name "unconnected-(U$2-PadB21)") (class "Default")
      (node (ref "U$2") (pin "B21") (pinfunction "B21_B21") (pintype "bidirectional"))
    )
    (net (code "93") (name "unconnected-(U$2-PadB22)") (class "Default")
      (node (ref "U$2") (pin "B22") (pinfunction "B22_B22") (pintype "bidirectional"))
    )
    (net (code "94") (name "unconnected-(U$2-PadB23)") (class "Default")
      (node (ref "U$2") (pin "B23") (pinfunction "B23_B23") (pintype "bidirectional"))
    )
    (net (code "95") (name "unconnected-(U$2-PadB24)") (class "Default")
      (node (ref "U$2") (pin "B24") (pinfunction "B24_B24") (pintype "bidirectional"))
    )
    (net (code "96") (name "unconnected-(U$2-PadB25)") (class "Default")
      (node (ref "U$2") (pin "B25") (pinfunction "B25_B25") (pintype "bidirectional"))
    )
    (net (code "97") (name "unconnected-(U$2-PadB26)") (class "Default")
      (node (ref "U$2") (pin "B26") (pinfunction "B26_B26") (pintype "bidirectional"))
    )
    (net (code "98") (name "unconnected-(U$2-PadB27)") (class "Default")
      (node (ref "U$2") (pin "B27") (pinfunction "B27_B27") (pintype "bidirectional"))
    )
    (net (code "99") (name "unconnected-(U$2-PadB28)") (class "Default")
      (node (ref "U$2") (pin "B28") (pinfunction "B28_B28") (pintype "bidirectional"))
    )
    (net (code "100") (name "unconnected-(U$2-PadB31)") (class "Default")
      (node (ref "U$2") (pin "B31") (pinfunction "B31_B31") (pintype "bidirectional"))
    )
    (net (code "101") (name "unconnected-(U$2-PadB32)") (class "Default")
      (node (ref "U$2") (pin "B32") (pinfunction "B32_B32") (pintype "bidirectional"))
    )
    (net (code "102") (name "unconnected-(U$2-PadB34)") (class "Default")
      (node (ref "U$2") (pin "B34") (pinfunction "B34_B34") (pintype "bidirectional"))
    )
    (net (code "103") (name "unconnected-(U$2-PadB36)") (class "Default")
      (node (ref "U$2") (pin "B36") (pinfunction "B36_B36") (pintype "bidirectional"))
    )
    (net (code "104") (name "unconnected-(U$2-PadB37)") (class "Default")
      (node (ref "U$2") (pin "B37") (pinfunction "B37_B37") (pintype "bidirectional"))
    )
    (net (code "105") (name "unconnected-(U$2-PadB38)") (class "Default")
      (node (ref "U$2") (pin "B38") (pinfunction "B38_B38") (pintype "bidirectional"))
    )
    (net (code "106") (name "unconnected-(U$2-PadB39)") (class "Default")
      (node (ref "U$2") (pin "B39") (pinfunction "B39_B39") (pintype "bidirectional"))
    )
    (net (code "107") (name "unconnected-(U$2-PadB40)") (class "Default")
      (node (ref "U$2") (pin "B40") (pinfunction "B40_B40") (pintype "bidirectional"))
    )
    (net (code "108") (name "unconnected-(U$2-PadT5)") (class "Default")
      (node (ref "U$2") (pin "T5") (pinfunction "T5_T5") (pintype "bidirectional"))
    )
    (net (code "109") (name "unconnected-(U$2-PadT6)") (class "Default")
      (node (ref "U$2") (pin "T6") (pinfunction "T6_T6") (pintype "bidirectional"))
    )
    (net (code "110") (name "unconnected-(U$2-PadT7)") (class "Default")
      (node (ref "U$2") (pin "T7") (pinfunction "T7_T7") (pintype "bidirectional"))
    )
    (net (code "111") (name "unconnected-(U$2-PadT8)") (class "Default")
      (node (ref "U$2") (pin "T8") (pinfunction "T8_T8") (pintype "bidirectional"))
    )
    (net (code "112") (name "unconnected-(U$2-PadT9)") (class "Default")
      (node (ref "U$2") (pin "T9") (pinfunction "T9_T9") (pintype "bidirectional"))
    )
    (net (code "113") (name "unconnected-(U$2-PadT10)") (class "Default")
      (node (ref "U$2") (pin "T10") (pinfunction "T10_T10") (pintype "bidirectional"))
    )
    (net (code "114") (name "unconnected-(U$2-PadT18)") (class "Default")
      (node (ref "U$2") (pin "T18") (pinfunction "T18_T18") (pintype "bidirectional"))
    )
    (net (code "115") (name "unconnected-(U$2-PadT27)") (class "Default")
      (node (ref "U$2") (pin "T27") (pinfunction "T27_T27") (pintype "bidirectional"))
    )
    (net (code "116") (name "unconnected-(U$2-PadT28)") (class "Default")
      (node (ref "U$2") (pin "T28") (pinfunction "T28_T28") (pintype "bidirectional"))
    )
    (net (code "117") (name "unconnected-(U$2-PadT29)") (class "Default")
      (node (ref "U$2") (pin "T29") (pinfunction "T29_T29") (pintype "bidirectional"))
    )
    (net (code "118") (name "unconnected-(U$2-PadT30)") (class "Default")
      (node (ref "U$2") (pin "T30") (pinfunction "T30_T30") (pintype "bidirectional"))
    )
    (net (code "119") (name "unconnected-(U$2-PadT31)") (class "Default")
      (node (ref "U$2") (pin "T31") (pinfunction "T31_T31") (pintype "bidirectional"))
    )
    (net (code "120") (name "unconnected-(U$2-PadT32)") (class "Default")
      (node (ref "U$2") (pin "T32") (pinfunction "T32_T32") (pintype "bidirectional"))
    )
    (net (code "121") (name "unconnected-(U$2-PadT33)") (class "Default")
      (node (ref "U$2") (pin "T33") (pinfunction "T33_T33") (pintype "bidirectional"))
    )
    (net (code "122") (name "unconnected-(U$2-PadT34)") (class "Default")
      (node (ref "U$2") (pin "T34") (pinfunction "T34_T34") (pintype "bidirectional"))
    )
    (net (code "123") (name "unconnected-(U$2-PadT35)") (class "Default")
      (node (ref "U$2") (pin "T35") (pinfunction "T35_T35") (pintype "bidirectional"))
    )
    (net (code "124") (name "unconnected-(U$2-PadT36)") (class "Default")
      (node (ref "U$2") (pin "T36") (pinfunction "T36_T36") (pintype "bidirectional"))
    )
    (net (code "125") (name "unconnected-(U$2-PadT37)") (class "Default")
      (node (ref "U$2") (pin "T37") (pinfunction "T37_T37") (pintype "bidirectional"))
    )
    (net (code "126") (name "unconnected-(U$2-PadT38)") (class "Default")
      (node (ref "U$2") (pin "T38") (pinfunction "T38_T38") (pintype "bidirectional"))
    )
    (net (code "127") (name "unconnected-(U$2-PadT39)") (class "Default")
      (node (ref "U$2") (pin "T39") (pinfunction "T39_T39") (pintype "bidirectional"))
    )
    (net (code "128") (name "unconnected-(U$2-PadT40)") (class "Default")
      (node (ref "U$2") (pin "T40") (pinfunction "T40_T40") (pintype "bidirectional"))
    )
    (net (code "129") (name "unconnected-(U1-IADJ-Pad2)") (class "Default")
      (node (ref "U1") (pin "2") (pinfunction "IADJ_2") (pintype "bidirectional"))
    )
    (net (code "130") (name "unconnected-(U2-SHDN-Pad5)") (class "Default")
      (node (ref "U2") (pin "5") (pinfunction "SHDN_5") (pintype "bidirectional"))
    )
    (net (code "131") (name "unconnected-(Y1-OE-Pad1)") (class "Default")
      (node (ref "Y1") (pin "1") (pinfunction "OE_1") (pintype "input"))
    )
  )
)
